# Power.net
KiCad netlist of a schematic drawn in Altium Designer
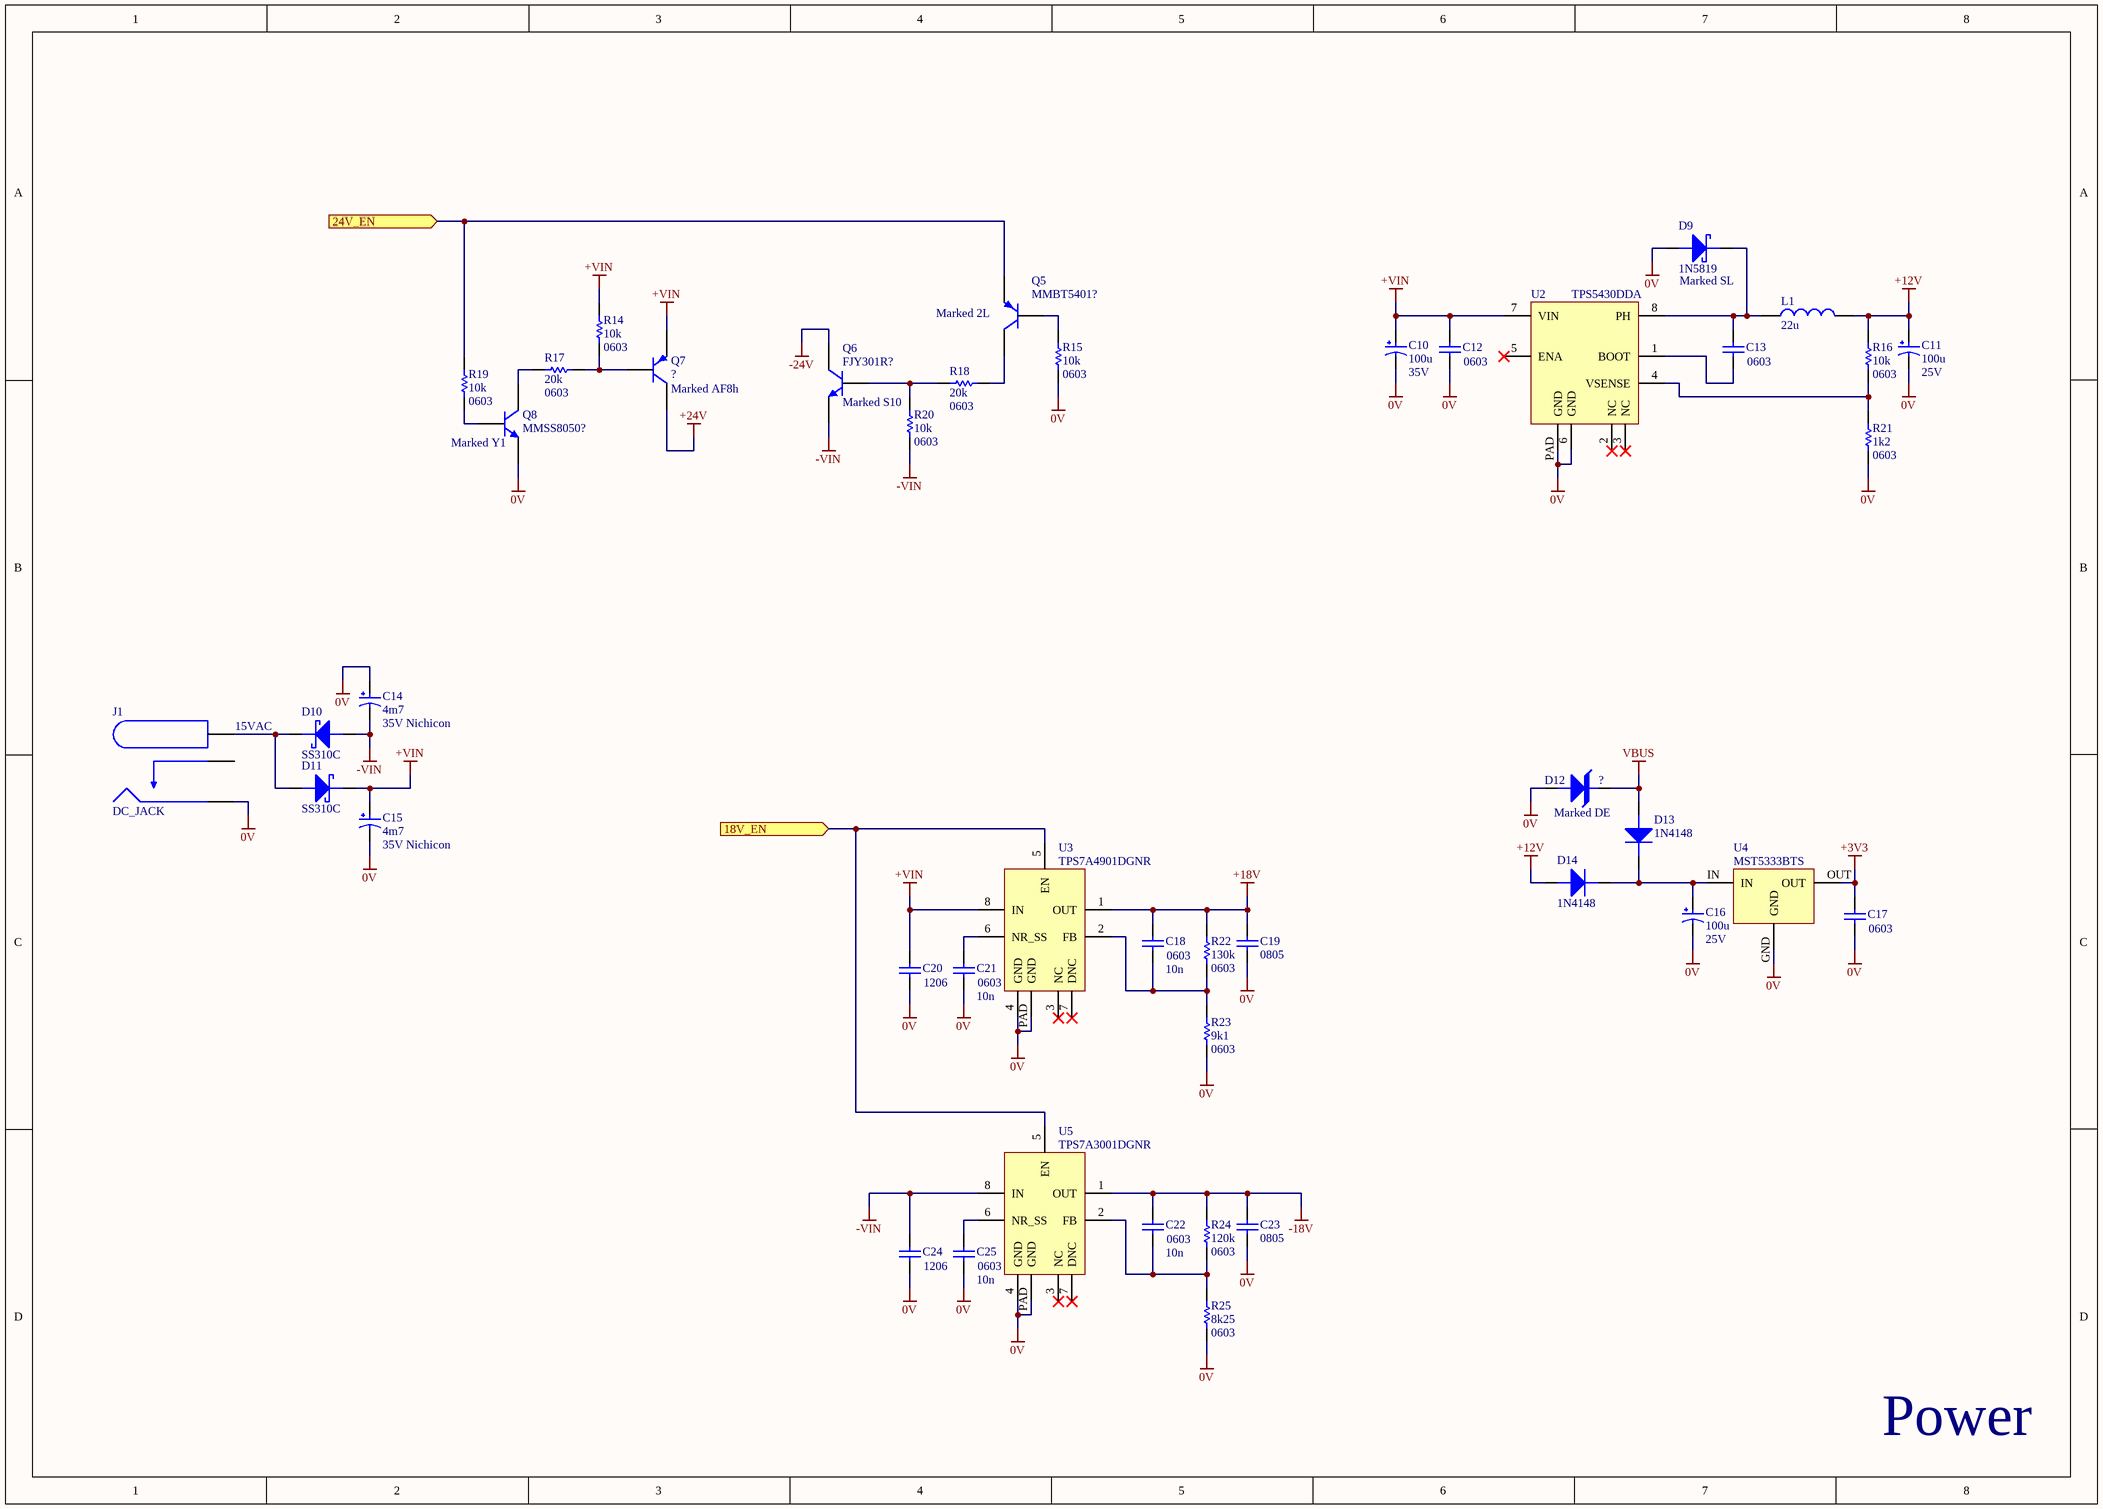
[diagram p0: Power.SchDoc]

(export (version "E")
  (design (tool "Eeschema 10.0.6"))
  (components
    (comp (ref "C10")
      (value "100u")
      (footprint "CAPAE13X20")
      (description "Alum. Electrolytic Cap 2200µF 16V 13mm Radial WCAP-ATLL; Lifetime 7000h +105°C")
      (fields
        (field (name "MANUFACTURER") "Würth Elektronik")
        (field (name "TOLERANCE") "20%")
        (field (name "NOTES") "35V")
      )
      (libsource (lib "Topping_L50") (part "860160378038"))
    )
    (comp (ref "C11")
      (value "100u")
      (footprint "CAPAE13X20")
      (description "Alum. Electrolytic Cap 2200µF 16V 13mm Radial WCAP-ATLL; Lifetime 7000h +105°C")
      (fields
        (field (name "MANUFACTURER") "Würth Elektronik")
        (field (name "TOLERANCE") "20%")
        (field (name "NOTES") "25V")
      )
      (libsource (lib "Topping_L50") (part "860160378038"))
    )
    (comp (ref "C12")
      (value "C_MLCC_0603")
      (footprint "CAPC1608X09N")
      (description "Generic MLCC 0603 Non Polarized Capacitor")
      (fields (field (name "MANUFACTURER") "Generic") (field (name "PACKAGE") "0603"))
      (libsource (lib "Topping_L50") (part "C_MLCC_0603"))
    )
    (comp (ref "C13")
      (value "C_MLCC_0603")
      (footprint "CAPC1608X09N")
      (description "Generic MLCC 0603 Non Polarized Capacitor")
      (fields (field (name "MANUFACTURER") "Generic") (field (name "PACKAGE") "0603"))
      (libsource (lib "Topping_L50") (part "C_MLCC_0603"))
    )
    (comp (ref "C14")
      (value "4m7")
      (footprint "CAPAE13X20")
      (description "Alum. Electrolytic Cap 2200µF 16V 13mm Radial WCAP-ATLL; Lifetime 7000h +105°C")
      (fields
        (field (name "MANUFACTURER") "Würth Elektronik")
        (field (name "TOLERANCE") "20%")
        (field (name "NOTES") "35V Nichicon")
      )
      (libsource (lib "Topping_L50") (part "860160378038"))
    )
    (comp (ref "C15")
      (value "4m7")
      (footprint "CAPAE13X20")
      (description "Alum. Electrolytic Cap 2200µF 16V 13mm Radial WCAP-ATLL; Lifetime 7000h +105°C")
      (fields
        (field (name "MANUFACTURER") "Würth Elektronik")
        (field (name "TOLERANCE") "20%")
        (field (name "NOTES") "35V Nichicon")
      )
      (libsource (lib "Topping_L50") (part "860160378038"))
    )
    (comp (ref "C16")
      (value "100u")
      (footprint "CAPAE13X20")
      (description "Alum. Electrolytic Cap 2200µF 16V 13mm Radial WCAP-ATLL; Lifetime 7000h +105°C")
      (fields
        (field (name "MANUFACTURER") "Würth Elektronik")
        (field (name "TOLERANCE") "20%")
        (field (name "NOTES") "25V")
      )
      (libsource (lib "Topping_L50") (part "860160378038"))
    )
    (comp (ref "C17")
      (value "C_MLCC_0603")
      (footprint "CAPC1608X09N")
      (description "Generic MLCC 0603 Non Polarized Capacitor")
      (fields (field (name "MANUFACTURER") "Generic") (field (name "PACKAGE") "0603"))
      (libsource (lib "Topping_L50") (part "C_MLCC_0603"))
    )
    (comp (ref "C18")
      (value "10n")
      (footprint "CAPC1608X09N")
      (description "Generic MLCC 0603 Non Polarized Capacitor")
      (fields
        (field (name "MANUFACTURER") "Generic")
        (field (name "PACKAGE") "0603")
        (field (name "Comment") "C_MLCC_0603")
      )
      (libsource (lib "Topping_L50") (part "C_MLCC_0603"))
    )
    (comp (ref "C19")
      (value "C_MLCC_0805")
      (footprint "CAPC2012X14N")
      (description "Generic MLCC 0805 Non Polarized Capacitor")
      (fields (field (name "MANUFACTURER") "Generic") (field (name "PACKAGE") "0805"))
      (libsource (lib "Topping_L50") (part "C_MLCC_0805"))
    )
    (comp (ref "C20")
      (value "C_MLCC_1206")
      (footprint "C_NP_1206")
      (description "Generic MLCC Non Polarized Capacitor 1206")
      (fields (field (name "MANUFACTURER") "Generic") (field (name "PACKAGE") "1206"))
      (libsource (lib "Topping_L50") (part "C_MLCC_1206"))
    )
    (comp (ref "C21")
      (value "10n")
      (footprint "CAPC1608X09N")
      (description "Generic MLCC 0603 Non Polarized Capacitor")
      (fields
        (field (name "MANUFACTURER") "Generic")
        (field (name "PACKAGE") "0603")
        (field (name "Comment") "C_MLCC_0603")
      )
      (libsource (lib "Topping_L50") (part "C_MLCC_0603"))
    )
    (comp (ref "C22")
      (value "10n")
      (footprint "CAPC1608X09N")
      (description "Generic MLCC 0603 Non Polarized Capacitor")
      (fields
        (field (name "MANUFACTURER") "Generic")
        (field (name "PACKAGE") "0603")
        (field (name "Comment") "C_MLCC_0603")
      )
      (libsource (lib "Topping_L50") (part "C_MLCC_0603"))
    )
    (comp (ref "C23")
      (value "C_MLCC_0805")
      (footprint "CAPC2012X14N")
      (description "Generic MLCC 0805 Non Polarized Capacitor")
      (fields (field (name "MANUFACTURER") "Generic") (field (name "PACKAGE") "0805"))
      (libsource (lib "Topping_L50") (part "C_MLCC_0805"))
    )
    (comp (ref "C24")
      (value "C_MLCC_1206")
      (footprint "C_NP_1206")
      (description "Generic MLCC Non Polarized Capacitor 1206")
      (fields (field (name "MANUFACTURER") "Generic") (field (name "PACKAGE") "1206"))
      (libsource (lib "Topping_L50") (part "C_MLCC_1206"))
    )
    (comp (ref "C25")
      (value "10n")
      (footprint "CAPC1608X09N")
      (description "Generic MLCC 0603 Non Polarized Capacitor")
      (fields
        (field (name "MANUFACTURER") "Generic")
        (field (name "PACKAGE") "0603")
        (field (name "Comment") "C_MLCC_0603")
      )
      (libsource (lib "Topping_L50") (part "C_MLCC_0603"))
    )
    (comp (ref "D9")
      (value "1N5819")
      (description "Generic Schottky, 1N5819")
      (fields
        (field (name "MANUFACTURER") "Generic")
        (field (name "MANUFACTURER PART NUMBER") "SS3H10-E3/9AT")
      )
      (libsource (lib "Topping_L50") (part "1N5819"))
    )
    (comp (ref "D10")
      (value "SS310C")
      (footprint "DIOM6959X26N")
      (description "Rectifier Diode, Schottky, 1 Phase, 1 Element, 3A, 100V V(RRM), Silicon, DO-214AB")
      (fields
        (field (name "MANUFACTURER") "Generic")
        (field (name "MANUFACTURER PART NUMBER") "SS3H10-E3/9AT")
      )
      (libsource (lib "Topping_L50") (part "SS310C"))
    )
    (comp (ref "D11")
      (value "SS310C")
      (footprint "DIOM6959X26N")
      (description "Rectifier Diode, Schottky, 1 Phase, 1 Element, 3A, 100V V(RRM), Silicon, DO-214AB")
      (fields
        (field (name "MANUFACTURER") "Generic")
        (field (name "MANUFACTURER PART NUMBER") "SS3H10-E3/9AT")
      )
      (libsource (lib "Topping_L50") (part "SS310C"))
    )
    (comp (ref "D12")
      (value "?")
      (footprint "DIOM4336X24N")
      (description "Generic TVS diode")
      (fields (field (name "MANUFACTURER") "Bourns") (field (name "MANUFACTURER PART NUMBER") "SMBJ30A"))
      (libsource (lib "Topping_L50") (part "TVS"))
    )
    (comp (ref "D13")
      (value "1N4148")
      (description "Generic small signal diode")
      (fields (field (name "MANUFACTURER") "Generic") (field (name "MANUFACTURER PART NUMBER") "BAT48ZFILM"))
      (libsource (lib "Topping_L50") (part "1N4148"))
    )
    (comp (ref "D14")
      (value "1N4148")
      (description "Generic small signal diode")
      (fields (field (name "MANUFACTURER") "Generic") (field (name "MANUFACTURER PART NUMBER") "BAT48ZFILM"))
      (libsource (lib "Topping_L50") (part "1N4148"))
    )
    (comp (ref "J1")
      (value "DC_JACK")
      (footprint "DC_JACK")
      (description "Generic Switched Horizontal DC Jack")
      (fields (field (name "MANUFACTURER") "Generic"))
      (libsource (lib "Topping_L50") (part "DC_JACK"))
    )
    (comp (ref "L1")
      (value "22u")
      (description "Generic L")
      (fields
        (field (name "MANUFACTURER") "Generic")
        (field (name "MANUFACTURER PART NUMBER") "MPXV1D1054L150")
      )
      (libsource (lib "Topping_L50") (part "L"))
    )
    (comp (ref "Q5")
      (value "MMBT5401?")
      (footprint "SOT95P230X110-3N")
      (description "PNP Epitaxial Silicon Transistor")
      (fields (field (name "MANUFACTURER") "MCC") (field (name "MANUFACTURER PART NUMBER") "MMBT3904VL"))
      (libsource (lib "Topping_L50") (part "MMBT5401"))
    )
    (comp (ref "Q6")
      (value "FJY301R?")
      (footprint "SOT95P230X110-3N")
      (description "NPN General-Purpose\r\nAmplifier")
      (fields (field (name "MANUFACTURER") "On Semi") (field (name "MANUFACTURER PART NUMBER") "MMBT3904VL"))
      (libsource (lib "Topping_L50") (part "MMBT5551"))
    )
    (comp (ref "Q7")
      (value "?")
      (footprint "SOT95P230X110-3N")
      (description "PNP Epitaxial Silicon Transistor")
      (fields (field (name "MANUFACTURER") "MCC") (field (name "MANUFACTURER PART NUMBER") "MMBT3904VL"))
      (libsource (lib "Topping_L50") (part "MMBT5401"))
    )
    (comp (ref "Q8")
      (value "MMSS8050?")
      (footprint "SOT95P230X110-3N")
      (description "NPN General-Purpose\r\nAmplifier")
      (fields (field (name "MANUFACTURER") "On Semi") (field (name "MANUFACTURER PART NUMBER") "MMBT3904VL"))
      (libsource (lib "Topping_L50") (part "MMBT5551"))
    )
    (comp (ref "R14")
      (value "10k")
      (footprint "RESC1608X06N")
      (description "Generic 0603 Single Resistor")
      (fields
        (field (name "MANUFACTURER") "Generic")
        (field (name "PACKAGE") "0603")
        (field (name "Comment") "R")
      )
      (libsource (lib "Topping_L50") (part "R_0603"))
    )
    (comp (ref "R15")
      (value "10k")
      (footprint "RESC1608X06N")
      (description "Generic 0603 Single Resistor")
      (fields
        (field (name "MANUFACTURER") "Generic")
        (field (name "PACKAGE") "0603")
        (field (name "Comment") "R")
      )
      (libsource (lib "Topping_L50") (part "R_0603"))
    )
    (comp (ref "R16")
      (value "10k")
      (footprint "RESC1608X06N")
      (description "Generic 0603 Single Resistor")
      (fields
        (field (name "MANUFACTURER") "Generic")
        (field (name "PACKAGE") "0603")
        (field (name "Comment") "R")
      )
      (libsource (lib "Topping_L50") (part "R_0603"))
    )
    (comp (ref "R17")
      (value "20k")
      (footprint "RESC1608X06N")
      (description "Generic 0603 Single Resistor")
      (fields
        (field (name "MANUFACTURER") "Generic")
        (field (name "PACKAGE") "0603")
        (field (name "Comment") "R")
      )
      (libsource (lib "Topping_L50") (part "R_0603"))
    )
    (comp (ref "R18")
      (value "20k")
      (footprint "RESC1608X06N")
      (description "Generic 0603 Single Resistor")
      (fields
        (field (name "MANUFACTURER") "Generic")
        (field (name "PACKAGE") "0603")
        (field (name "Comment") "R")
      )
      (libsource (lib "Topping_L50") (part "R_0603"))
    )
    (comp (ref "R19")
      (value "10k")
      (footprint "RESC1608X06N")
      (description "Generic 0603 Single Resistor")
      (fields
        (field (name "MANUFACTURER") "Generic")
        (field (name "PACKAGE") "0603")
        (field (name "Comment") "R")
      )
      (libsource (lib "Topping_L50") (part "R_0603"))
    )
    (comp (ref "R20")
      (value "10k")
      (footprint "RESC1608X06N")
      (description "Generic 0603 Single Resistor")
      (fields
        (field (name "MANUFACTURER") "Generic")
        (field (name "PACKAGE") "0603")
        (field (name "Comment") "R")
      )
      (libsource (lib "Topping_L50") (part "R_0603"))
    )
    (comp (ref "R21")
      (value "1k2")
      (footprint "RESC1608X06N")
      (description "Generic 0603 Single Resistor")
      (fields
        (field (name "MANUFACTURER") "Generic")
        (field (name "PACKAGE") "0603")
        (field (name "Comment") "R")
      )
      (libsource (lib "Topping_L50") (part "R_0603"))
    )
    (comp (ref "R22")
      (value "130k")
      (footprint "RESC1608X06N")
      (description "Generic 0603 Single Resistor")
      (fields
        (field (name "MANUFACTURER") "Generic")
        (field (name "PACKAGE") "0603")
        (field (name "Comment") "R")
      )
      (libsource (lib "Topping_L50") (part "R_0603"))
    )
    (comp (ref "R23")
      (value "9k1")
      (footprint "RESC1608X06N")
      (description "Generic 0603 Single Resistor")
      (fields
        (field (name "MANUFACTURER") "Generic")
        (field (name "PACKAGE") "0603")
        (field (name "Comment") "R")
      )
      (libsource (lib "Topping_L50") (part "R_0603"))
    )
    (comp (ref "R24")
      (value "120k")
      (footprint "RESC1608X06N")
      (description "Generic 0603 Single Resistor")
      (fields
        (field (name "MANUFACTURER") "Generic")
        (field (name "PACKAGE") "0603")
        (field (name "Comment") "R")
      )
      (libsource (lib "Topping_L50") (part "R_0603"))
    )
    (comp (ref "R25")
      (value "8k25")
      (footprint "RESC1608X06N")
      (description "Generic 0603 Single Resistor")
      (fields
        (field (name "MANUFACTURER") "Generic")
        (field (name "PACKAGE") "0603")
        (field (name "Comment") "R")
      )
      (libsource (lib "Topping_L50") (part "R_0603"))
    )
    (comp (ref "U2")
      (value "TPS5430DDA")
      (footprint "SOIC127P600X170_HS-9N")
      (description "Wide Input Range, Step-Down Converter")
      (fields (field (name "MANUFACTURER") "Texas Instruments"))
      (libsource (lib "Topping_L50") (part "TPS5430DDA"))
    )
    (comp (ref "U3")
      (value "TPS7A4901DGNR")
      (footprint "TSOP65P490X110_HS-9N")
      (description "–35-V, –200-mA, Ultralow-Noise, Positive Linear Regulator")
      (fields (field (name "MANUFACTURER") "Texas Instruments"))
      (libsource (lib "Topping_L50") (part "TPS7A4901DGNR"))
    )
    (comp (ref "U4")
      (value "MST5333BTS")
      (footprint "SOT89-150P410X160-3N")
      (description "Fixed Positive Standard Regulator, 3.3VBIPolar, PSSO3")
      (fields
        (field (name "MANUFACTURER") "Milestone Semiconductor Inc.")
        (field (name "MANUFACTURER PART NUMBER") "L78L33ACUTR")
      )
      (libsource (lib "Topping_L50") (part "MST5333BTS"))
    )
    (comp (ref "U5")
      (value "TPS7A3001DGNR")
      (footprint "TSOP65P490X110_HS-9N")
      (description "–35-V, –200-mA, Ultralow-Noise, Negative Linear Regulator")
      (fields (field (name "MANUFACTURER") "Texas Instruments"))
      (libsource (lib "Topping_L50") (part "TPS7A3001DGNR"))
    )
  )
  (nets
    (net (code "1") (name "+3V3") (class "Default")
      (node (ref "C17") (pin "2") (pinfunction "2_2") (pintype "passive"))
      (node (ref "U4") (pin "OUT") (pinfunction "OUT_OUT") (pintype "passive"))
    )
    (net (code "2") (name "+12V") (class "Default")
      (node (ref "C11") (pin "+") (pinfunction "+_+") (pintype "passive"))
      (node (ref "D14") (pin "A") (pinfunction "A_A") (pintype "passive"))
      (node (ref "L1") (pin "2") (pinfunction "2_2") (pintype "passive"))
      (node (ref "R16") (pin "2") (pinfunction "2_2") (pintype "passive"))
    )
    (net (code "3") (name "+18V") (class "Default")
      (node (ref "C18") (pin "2") (pinfunction "2_2") (pintype "passive"))
      (node (ref "C19") (pin "2") (pinfunction "2_2") (pintype "passive"))
      (node (ref "R22") (pin "2") (pinfunction "2_2") (pintype "passive"))
      (node (ref "U3") (pin "1") (pinfunction "OUT_1") (pintype "passive"))
    )
    (net (code "4") (name "+24V") (class "Default")
      (node (ref "Q7") (pin "C") (pinfunction "C_C") (pintype "passive"))
    )
    (net (code "5") (name "+VIN") (class "Default")
      (node (ref "C10") (pin "+") (pinfunction "+_+") (pintype "passive"))
      (node (ref "C12") (pin "2") (pinfunction "2_2") (pintype "passive"))
      (node (ref "C15") (pin "+") (pinfunction "+_+") (pintype "passive"))
      (node (ref "C20") (pin "2") (pinfunction "2_2") (pintype "passive"))
      (node (ref "D11") (pin "K") (pinfunction "K_K") (pintype "passive"))
      (node (ref "Q7") (pin "E") (pinfunction "E_E") (pintype "passive"))
      (node (ref "R14") (pin "1") (pinfunction "1_1") (pintype "passive"))
      (node (ref "U2") (pin "7") (pinfunction "VIN_7") (pintype "passive"))
      (node (ref "U3") (pin "8") (pinfunction "IN_8") (pintype "passive"))
    )
    (net (code "6") (name "-18V") (class "Default")
      (node (ref "C22") (pin "2") (pinfunction "2_2") (pintype "passive"))
      (node (ref "C23") (pin "2") (pinfunction "2_2") (pintype "passive"))
      (node (ref "R24") (pin "2") (pinfunction "2_2") (pintype "passive"))
      (node (ref "U5") (pin "1") (pinfunction "OUT_1") (pintype "passive"))
    )
    (net (code "7") (name "-24V") (class "Default")
      (node (ref "Q6") (pin "C") (pinfunction "C_C") (pintype "passive"))
    )
    (net (code "8") (name "-VIN") (class "Default")
      (node (ref "C14") (pin "-") (pinfunction "-_-") (pintype "passive"))
      (node (ref "C24") (pin "2") (pinfunction "2_2") (pintype "passive"))
      (node (ref "D10") (pin "A") (pinfunction "A_A") (pintype "passive"))
      (node (ref "Q6") (pin "E") (pinfunction "E_E") (pintype "passive"))
      (node (ref "R20") (pin "2") (pinfunction "2_2") (pintype "passive"))
      (node (ref "U5") (pin "8") (pinfunction "IN_8") (pintype "passive"))
    )
    (net (code "9") (name "/18V_EN") (class "Default")
      (node (ref "U3") (pin "5") (pinfunction "EN_5") (pintype "passive"))
      (node (ref "U5") (pin "5") (pinfunction "EN_5") (pintype "passive"))
    )
    (net (code "10") (name "/24V_EN") (class "Default")
      (node (ref "Q5") (pin "E") (pinfunction "E_E") (pintype "passive"))
      (node (ref "R19") (pin "1") (pinfunction "1_1") (pintype "passive"))
    )
    (net (code "11") (name "0V") (class "Default")
      (node (ref "C10") (pin "-") (pinfunction "-_-") (pintype "passive"))
      (node (ref "C11") (pin "-") (pinfunction "-_-") (pintype "passive"))
      (node (ref "C12") (pin "1") (pinfunction "1_1") (pintype "passive"))
      (node (ref "C14") (pin "+") (pinfunction "+_+") (pintype "passive"))
      (node (ref "C15") (pin "-") (pinfunction "-_-") (pintype "passive"))
      (node (ref "C16") (pin "-") (pinfunction "-_-") (pintype "passive"))
      (node (ref "C17") (pin "1") (pinfunction "1_1") (pintype "passive"))
      (node (ref "C19") (pin "1") (pinfunction "1_1") (pintype "passive"))
      (node (ref "C20") (pin "1") (pinfunction "1_1") (pintype "passive"))
      (node (ref "C21") (pin "1") (pinfunction "1_1") (pintype "passive"))
      (node (ref "C23") (pin "1") (pinfunction "1_1") (pintype "passive"))
      (node (ref "C24") (pin "1") (pinfunction "1_1") (pintype "passive"))
      (node (ref "C25") (pin "1") (pinfunction "1_1") (pintype "passive"))
      (node (ref "D12") (pin "A") (pinfunction "A_A") (pintype "passive"))
      (node (ref "D9") (pin "A") (pinfunction "A_A") (pintype "passive"))
      (node (ref "J1") (pin "S") (pinfunction "S_S") (pintype "passive"))
      (node (ref "Q8") (pin "E") (pinfunction "E_E") (pintype "passive"))
      (node (ref "R15") (pin "1") (pinfunction "1_1") (pintype "passive"))
      (node (ref "R21") (pin "1") (pinfunction "1_1") (pintype "passive"))
      (node (ref "R23") (pin "1") (pinfunction "1_1") (pintype "passive"))
      (node (ref "R25") (pin "1") (pinfunction "1_1") (pintype "passive"))
      (node (ref "U2") (pin "6") (pinfunction "GND_6") (pintype "passive"))
      (node (ref "U2") (pin "PAD") (pinfunction "GND_PAD") (pintype "passive"))
      (node (ref "U3") (pin "4") (pinfunction "GND_4") (pintype "passive"))
      (node (ref "U3") (pin "PAD") (pinfunction "GND_PAD") (pintype "passive"))
      (node (ref "U4") (pin "GND") (pinfunction "GND_GND") (pintype "passive"))
      (node (ref "U5") (pin "4") (pinfunction "GND_4") (pintype "passive"))
      (node (ref "U5") (pin "PAD") (pinfunction "GND_PAD") (pintype "passive"))
    )
    (net (code "12") (name "Net-(C16-Pad+)") (class "Default")
      (node (ref "C16") (pin "+") (pinfunction "+_+") (pintype "passive"))
      (node (ref "D13") (pin "K") (pinfunction "K_K") (pintype "passive"))
      (node (ref "D14") (pin "K") (pinfunction "K_K") (pintype "passive"))
      (node (ref "U4") (pin "IN") (pinfunction "IN_IN") (pintype "passive"))
    )
    (net (code "13") (name "Net-(D10-PadK)") (class "Default")
      (node (ref "D10") (pin "K") (pinfunction "K_K") (pintype "passive"))
      (node (ref "D11") (pin "A") (pinfunction "A_A") (pintype "passive"))
      (node (ref "J1") (pin "T") (pinfunction "T_T") (pintype "passive"))
    )
    (net (code "14") (name "Net-(Q5-PadB)") (class "Default")
      (node (ref "Q5") (pin "B") (pinfunction "B_B") (pintype "passive"))
      (node (ref "R15") (pin "2") (pinfunction "2_2") (pintype "passive"))
    )
    (net (code "15") (name "Net-(Q5-PadC)") (class "Default")
      (node (ref "Q5") (pin "C") (pinfunction "C_C") (pintype "passive"))
      (node (ref "R18") (pin "1") (pinfunction "1_1") (pintype "passive"))
    )
    (net (code "16") (name "Net-(Q6-PadB)") (class "Default")
      (node (ref "Q6") (pin "B") (pinfunction "B_B") (pintype "passive"))
      (node (ref "R18") (pin "2") (pinfunction "2_2") (pintype "passive"))
      (node (ref "R20") (pin "1") (pinfunction "1_1") (pintype "passive"))
    )
    (net (code "17") (name "Net-(Q7-PadB)") (class "Default")
      (node (ref "Q7") (pin "B") (pinfunction "B_B") (pintype "passive"))
      (node (ref "R14") (pin "2") (pinfunction "2_2") (pintype "passive"))
      (node (ref "R17") (pin "1") (pinfunction "1_1") (pintype "passive"))
    )
    (net (code "18") (name "Net-(Q8-PadB)") (class "Default")
      (node (ref "Q8") (pin "B") (pinfunction "B_B") (pintype "passive"))
      (node (ref "R19") (pin "2") (pinfunction "2_2") (pintype "passive"))
    )
    (net (code "19") (name "Net-(Q8-PadC)") (class "Default")
      (node (ref "Q8") (pin "C") (pinfunction "C_C") (pintype "passive"))
      (node (ref "R17") (pin "2") (pinfunction "2_2") (pintype "passive"))
    )
    (net (code "20") (name "Net-(U2-BOOT)") (class "Default")
      (node (ref "C13") (pin "1") (pinfunction "1_1") (pintype "passive"))
      (node (ref "U2") (pin "1") (pinfunction "BOOT_1") (pintype "passive"))
    )
    (net (code "21") (name "Net-(U2-PH)") (class "Default")
      (node (ref "C13") (pin "2") (pinfunction "2_2") (pintype "passive"))
      (node (ref "D9") (pin "K") (pinfunction "K_K") (pintype "passive"))
      (node (ref "L1") (pin "1") (pinfunction "1_1") (pintype "passive"))
      (node (ref "U2") (pin "8") (pinfunction "PH_8") (pintype "passive"))
    )
    (net (code "22") (name "Net-(U2-VSENSE)") (class "Default")
      (node (ref "R16") (pin "1") (pinfunction "1_1") (pintype "passive"))
      (node (ref "R21") (pin "2") (pinfunction "2_2") (pintype "passive"))
      (node (ref "U2") (pin "4") (pinfunction "VSENSE_4") (pintype "passive"))
    )
    (net (code "23") (name "Net-(U3-FB)") (class "Default")
      (node (ref "C18") (pin "1") (pinfunction "1_1") (pintype "passive"))
      (node (ref "R22") (pin "1") (pinfunction "1_1") (pintype "passive"))
      (node (ref "R23") (pin "2") (pinfunction "2_2") (pintype "passive"))
      (node (ref "U3") (pin "2") (pinfunction "FB_2") (pintype "passive"))
    )
    (net (code "24") (name "Net-(U3-NR_SS)") (class "Default")
      (node (ref "C21") (pin "2") (pinfunction "2_2") (pintype "passive"))
      (node (ref "U3") (pin "6") (pinfunction "NR_SS_6") (pintype "passive"))
    )
    (net (code "25") (name "Net-(U5-FB)") (class "Default")
      (node (ref "C22") (pin "1") (pinfunction "1_1") (pintype "passive"))
      (node (ref "R24") (pin "1") (pinfunction "1_1") (pintype "passive"))
      (node (ref "R25") (pin "2") (pinfunction "2_2") (pintype "passive"))
      (node (ref "U5") (pin "2") (pinfunction "FB_2") (pintype "passive"))
    )
    (net (code "26") (name "Net-(U5-NR_SS)") (class "Default")
      (node (ref "C25") (pin "2") (pinfunction "2_2") (pintype "passive"))
      (node (ref "U5") (pin "6") (pinfunction "NR_SS_6") (pintype "passive"))
    )
    (net (code "27") (name "VBUS") (class "Default")
      (node (ref "D12") (pin "K") (pinfunction "K_K") (pintype "passive"))
      (node (ref "D13") (pin "A") (pinfunction "A_A") (pintype "passive"))
    )
    (net (code "28") (name "unconnected-(J1-PadSN)") (class "Default")
      (node (ref "J1") (pin "SN") (pinfunction "SN_SN") (pintype "passive"))
    )
    (net (code "29") (name "unconnected-(U2-ENA-Pad5)") (class "Default")
      (node (ref "U2") (pin "5") (pinfunction "ENA_5") (pintype "passive+no_connect"))
    )
    (net (code "30") (name "unconnected-(U2-NC-Pad2)") (class "Default")
      (node (ref "U2") (pin "2") (pinfunction "NC_2") (pintype "passive+no_connect"))
    )
    (net (code "31") (name "unconnected-(U2-NC-Pad3)") (class "Default")
      (node (ref "U2") (pin "3") (pinfunction "NC_3") (pintype "passive+no_connect"))
    )
    (net (code "32") (name "unconnected-(U3-DNC-Pad7)") (class "Default")
      (node (ref "U3") (pin "7") (pinfunction "DNC_7") (pintype "passive+no_connect"))
    )
    (net (code "33") (name "unconnected-(U3-NC-Pad3)") (class "Default")
      (node (ref "U3") (pin "3") (pinfunction "NC_3") (pintype "passive+no_connect"))
    )
    (net (code "34") (name "unconnected-(U5-DNC-Pad7)") (class "Default")
      (node (ref "U5") (pin "7") (pinfunction "DNC_7") (pintype "passive+no_connect"))
    )
    (net (code "35") (name "unconnected-(U5-NC-Pad3)") (class "Default")
      (node (ref "U5") (pin "3") (pinfunction "NC_3") (pintype "passive+no_connect"))
    )
  )
)
